# Board_Vesion_1_27_2015.net
KiCad netlist of a schematic drawn in EAGLE
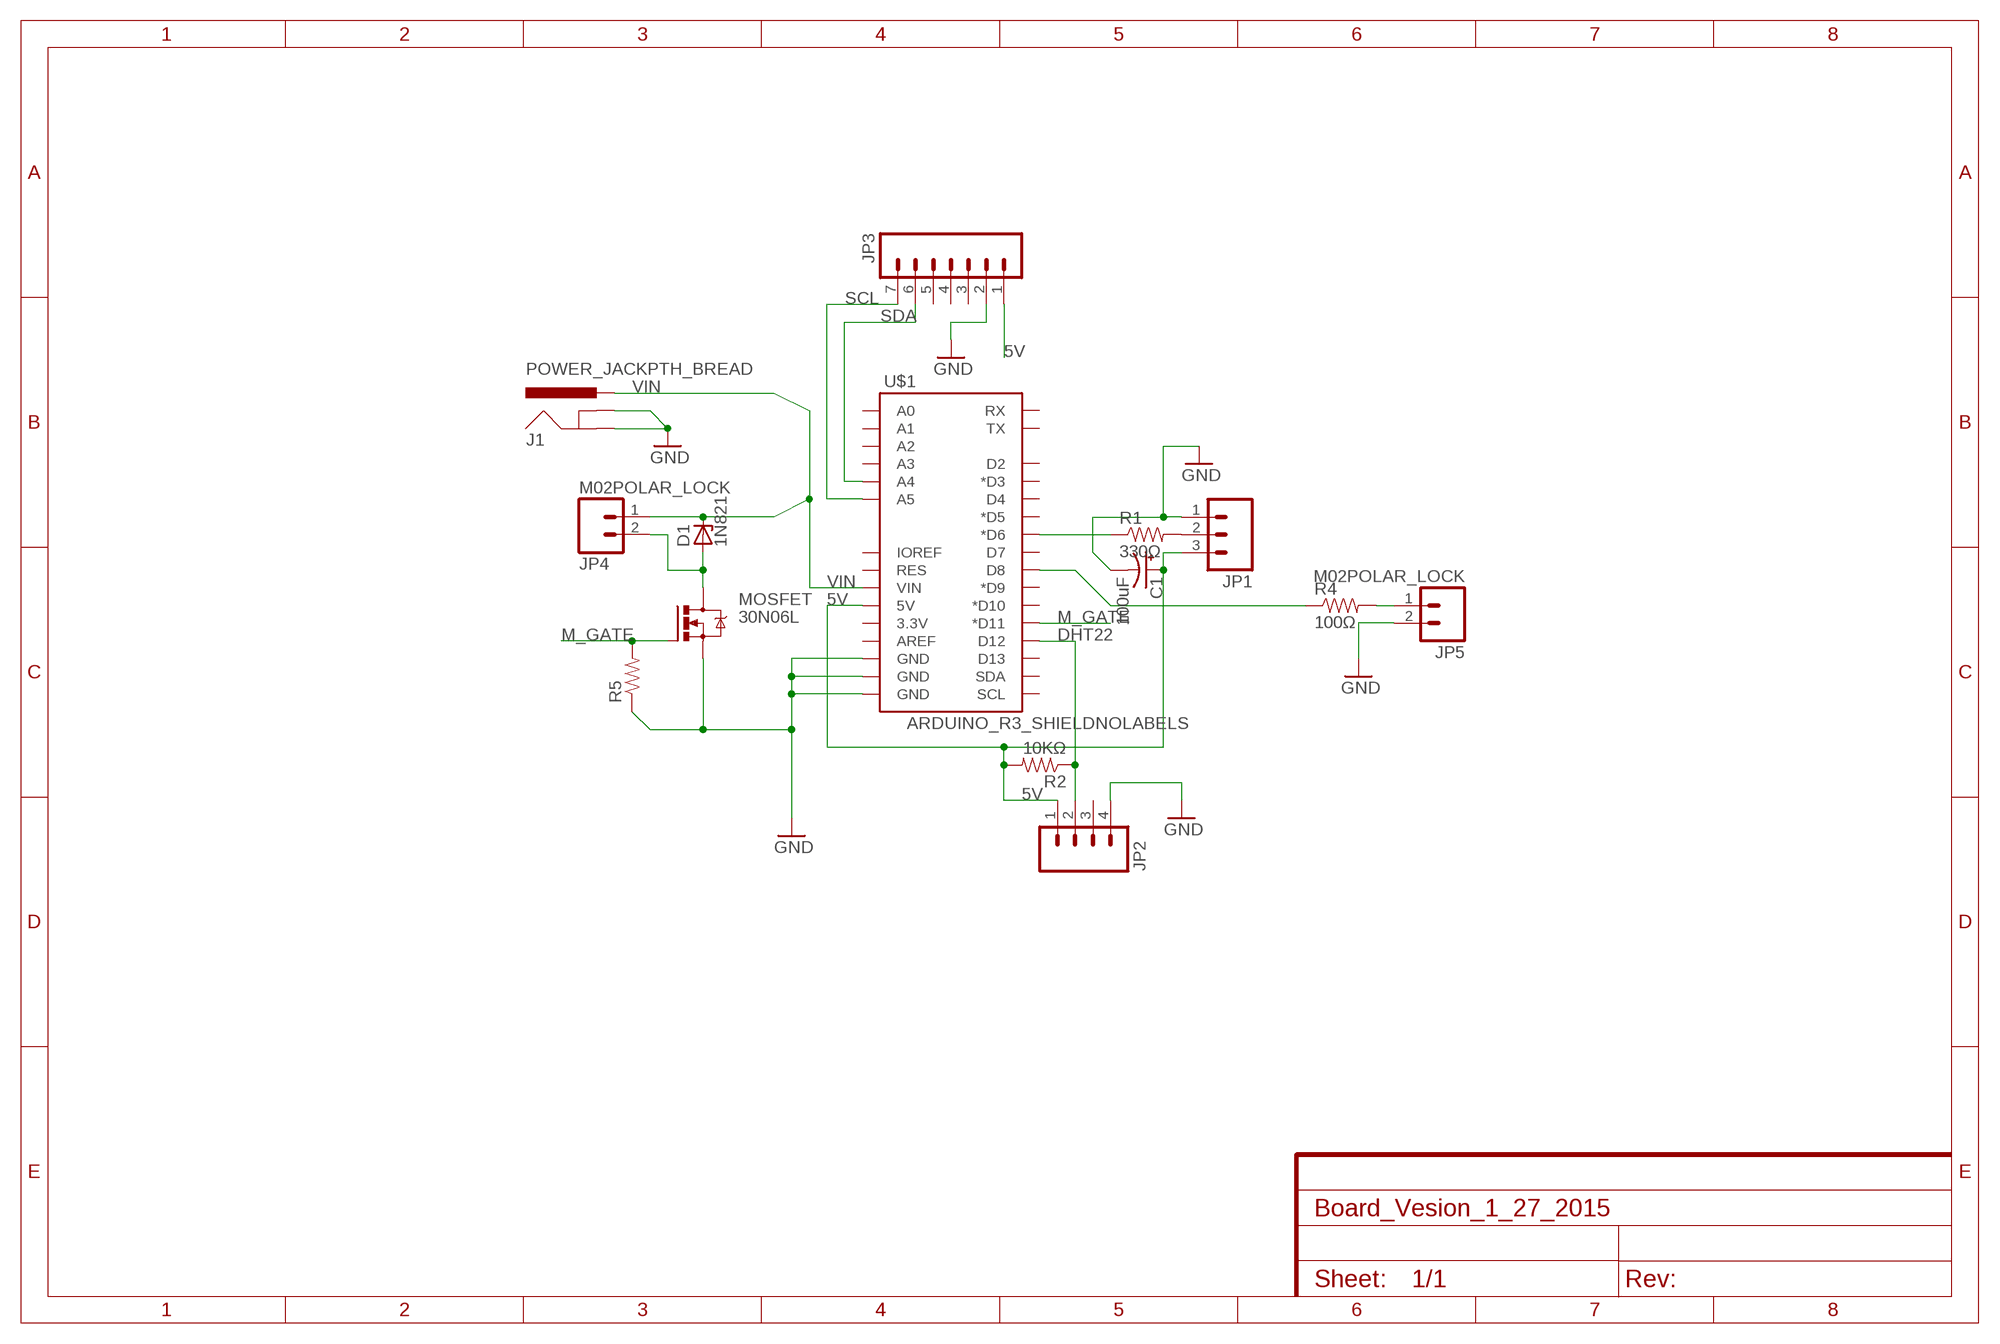
[diagram p0: schematic, sheet 1]

(export (version "E")
  (design (tool "Eeschema 10.0.6"))
  (components
    (comp (ref "C1")
      (value "100uF")
      (footprint "eagle-import:CPOL-RADIAL-10UF-25V")
      (libsource (lib "eagle-import") (part "CAP_POLPTH2"))
    )
    (comp (ref "D1")
      (value "1N821")
      (footprint "eagle-import:DO35Z10")
      (libsource (lib "eagle-import") (part "1N821"))
    )
    (comp (ref "J1")
      (value "POWER_JACKPTH_BREAD")
      (footprint "eagle-import:POWER_JACK_PTH_BREAD")
      (libsource (lib "eagle-import") (part "POWER_JACKPTH_BREAD"))
    )
    (comp (ref "JP1")
      (value "M03LOCK_LONGPADS")
      (footprint "eagle-import:1X03_LOCK_LONGPADS")
      (libsource (lib "eagle-import") (part "M03LOCK_LONGPADS"))
    )
    (comp (ref "JP2")
      (value "M04LOCK_LONGPADS")
      (footprint "eagle-import:1X04_LOCK_LONGPADS")
      (libsource (lib "eagle-import") (part "M04LOCK_LONGPADS"))
    )
    (comp (ref "JP3")
      (value "M07LOCK_LONGPADS")
      (footprint "eagle-import:1X07_LOCK_LONGPADS")
      (libsource (lib "eagle-import") (part "M07LOCK_LONGPADS"))
    )
    (comp (ref "JP4")
      (value "M02POLAR_LOCK")
      (footprint "eagle-import:MOLEX-1X2_LOCK")
      (libsource (lib "eagle-import") (part "M02POLAR_LOCK"))
    )
    (comp (ref "JP5")
      (value "M02POLAR_LOCK")
      (footprint "eagle-import:MOLEX-1X2_LOCK")
      (libsource (lib "eagle-import") (part "M02POLAR_LOCK"))
    )
    (comp (ref "MOSFET")
      (value "30N06L")
      (footprint "eagle-import:TO220BV")
      (libsource (lib "eagle-import") (part "IRF740"))
    )
    (comp (ref "R1")
      (value "330Ω")
      (footprint "eagle-import:AXIAL-0.4")
      (libsource (lib "eagle-import") (part "RESISTORPTH-1/4W"))
    )
    (comp (ref "R2")
      (value "10KΩ")
      (footprint "eagle-import:AXIAL-0.4")
      (libsource (lib "eagle-import") (part "RESISTORPTH-1/4W"))
    )
    (comp (ref "R4")
      (value "100Ω")
      (footprint "eagle-import:AXIAL-0.4")
      (libsource (lib "eagle-import") (part "SparkFun-Resistors_RESISTORPTH-1/4W"))
    )
    (comp (ref "R5")
      (value "RESISTORPTH-1W")
      (footprint "eagle-import:AXIAL-0.6")
      (libsource (lib "eagle-import") (part "SparkFun-Resistors_RESISTORPTH-1W"))
    )
    (comp (ref "U$1")
      (value "ARDUINO_R3_SHIELDNOLABELS")
      (footprint "eagle-import:UNO_R3_SHIELD_NOLABELS")
      (libsource (lib "eagle-import") (part "ARDUINO_R3_SHIELDNOLABELS"))
    )
  )
  (nets
    (net (code "1") (name "/5V") (class "Default")
      (node (ref "C1") (pin "1") (pinfunction "+_1") (pintype "passive"))
      (node (ref "JP1") (pin "3") (pinfunction "3_3") (pintype "passive"))
      (node (ref "JP2") (pin "1") (pinfunction "1_1") (pintype "passive"))
      (node (ref "JP3") (pin "1") (pinfunction "1_1") (pintype "passive"))
      (node (ref "R2") (pin "P$2") (pinfunction "2_P$2") (pintype "passive"))
      (node (ref "U$1") (pin "5V") (pinfunction "5V_5V") (pintype "bidirectional"))
    )
    (net (code "2") (name "/DHT22") (class "Default")
      (node (ref "JP2") (pin "2") (pinfunction "2_2") (pintype "passive"))
      (node (ref "R2") (pin "P$1") (pinfunction "1_P$1") (pintype "passive"))
      (node (ref "U$1") (pin "D12") (pinfunction "D12_D12") (pintype "bidirectional"))
    )
    (net (code "3") (name "/M_GATE") (class "Default")
      (node (ref "MOSFET") (pin "G") (pinfunction "G_G") (pintype "passive"))
      (node (ref "R5") (pin "P$2") (pinfunction "2_P$2") (pintype "passive"))
      (node (ref "U$1") (pin "D11") (pinfunction "*D11_D11") (pintype "bidirectional"))
    )
    (net (code "4") (name "/SCL") (class "Default")
      (node (ref "JP3") (pin "7") (pinfunction "7_7") (pintype "passive"))
      (node (ref "U$1") (pin "A5") (pinfunction "A5_A5") (pintype "bidirectional"))
    )
    (net (code "5") (name "/SDA") (class "Default")
      (node (ref "JP3") (pin "6") (pinfunction "6_6") (pintype "passive"))
      (node (ref "U$1") (pin "A4") (pinfunction "A4_A4") (pintype "bidirectional"))
    )
    (net (code "6") (name "/VIN") (class "Default")
      (node (ref "D1") (pin "C") (pinfunction "C_C") (pintype "passive"))
      (node (ref "J1") (pin "PWR") (pinfunction "PWR_PWR") (pintype "bidirectional"))
      (node (ref "JP4") (pin "1") (pinfunction "1_1") (pintype "passive"))
      (node (ref "U$1") (pin "VIN") (pinfunction "VIN_VIN") (pintype "bidirectional"))
    )
    (net (code "7") (name "GND") (class "Default")
      (node (ref "C1") (pin "2") (pinfunction "-_2") (pintype "passive"))
      (node (ref "J1") (pin "GND") (pinfunction "GND_GND") (pintype "bidirectional"))
      (node (ref "J1") (pin "GNDBREAK") (pinfunction "GNDBREAK_GNDBREAK") (pintype "bidirectional"))
      (node (ref "JP1") (pin "1") (pinfunction "1_1") (pintype "passive"))
      (node (ref "JP2") (pin "4") (pinfunction "4_4") (pintype "passive"))
      (node (ref "JP3") (pin "2") (pinfunction "2_2") (pintype "passive"))
      (node (ref "JP5") (pin "2") (pinfunction "2_2") (pintype "passive"))
      (node (ref "MOSFET") (pin "S") (pinfunction "S_S") (pintype "passive"))
      (node (ref "R5") (pin "P$1") (pinfunction "1_P$1") (pintype "passive"))
      (node (ref "U$1") (pin "GND@0") (pinfunction "GND_GND@0") (pintype "bidirectional"))
      (node (ref "U$1") (pin "GND@1") (pinfunction "GND_GND@1") (pintype "bidirectional"))
      (node (ref "U$1") (pin "GND@2") (pinfunction "GND_GND@2") (pintype "bidirectional"))
    )
    (net (code "8") (name "Net-(D1-PadA)") (class "Default")
      (node (ref "D1") (pin "A") (pinfunction "A_A") (pintype "passive"))
      (node (ref "JP4") (pin "2") (pinfunction "2_2") (pintype "passive"))
      (node (ref "MOSFET") (pin "D") (pinfunction "D_D") (pintype "passive"))
    )
    (net (code "9") (name "Net-(R1-1)") (class "Default")
      (node (ref "R1") (pin "P$1") (pinfunction "1_P$1") (pintype "passive"))
      (node (ref "U$1") (pin "D6") (pinfunction "*D6_D6") (pintype "bidirectional"))
    )
    (net (code "10") (name "Net-(R1-2)") (class "Default")
      (node (ref "JP1") (pin "2") (pinfunction "2_2") (pintype "passive"))
      (node (ref "R1") (pin "P$2") (pinfunction "2_P$2") (pintype "passive"))
    )
    (net (code "11") (name "Net-(R4-1)") (class "Default")
      (node (ref "R4") (pin "P$1") (pinfunction "1_P$1") (pintype "passive"))
      (node (ref "U$1") (pin "D8") (pinfunction "D8_D8") (pintype "bidirectional"))
    )
    (net (code "12") (name "Net-(R4-2)") (class "Default")
      (node (ref "JP5") (pin "1") (pinfunction "1_1") (pintype "passive"))
      (node (ref "R4") (pin "P$2") (pinfunction "2_P$2") (pintype "passive"))
    )
    (net (code "13") (name "unconnected-(JP2-Pad3)") (class "Default")
      (node (ref "JP2") (pin "3") (pinfunction "3_3") (pintype "passive"))
    )
    (net (code "14") (name "unconnected-(JP3-Pad3)") (class "Default")
      (node (ref "JP3") (pin "3") (pinfunction "3_3") (pintype "passive"))
    )
    (net (code "15") (name "unconnected-(JP3-Pad4)") (class "Default")
      (node (ref "JP3") (pin "4") (pinfunction "4_4") (pintype "passive"))
    )
    (net (code "16") (name "unconnected-(JP3-Pad5)") (class "Default")
      (node (ref "JP3") (pin "5") (pinfunction "5_5") (pintype "passive"))
    )
    (net (code "17") (name "unconnected-(U$1-*D3-PadD3)") (class "Default")
      (node (ref "U$1") (pin "D3") (pinfunction "*D3_D3") (pintype "bidirectional"))
    )
    (net (code "18") (name "unconnected-(U$1-*D5-PadD5)") (class "Default")
      (node (ref "U$1") (pin "D5") (pinfunction "*D5_D5") (pintype "bidirectional"))
    )
    (net (code "19") (name "unconnected-(U$1-*D9-PadD9)") (class "Default")
      (node (ref "U$1") (pin "D9") (pinfunction "*D9_D9") (pintype "bidirectional"))
    )
    (net (code "20") (name "unconnected-(U$1-*D10-PadD10)") (class "Default")
      (node (ref "U$1") (pin "D10") (pinfunction "*D10_D10") (pintype "bidirectional"))
    )
    (net (code "21") (name "unconnected-(U$1-Pad3.3V)") (class "Default")
      (node (ref "U$1") (pin "3.3V") (pinfunction "3.3V_3.3V") (pintype "bidirectional"))
    )
    (net (code "22") (name "unconnected-(U$1-PadA0)") (class "Default")
      (node (ref "U$1") (pin "A0") (pinfunction "A0_A0") (pintype "bidirectional"))
    )
    (net (code "23") (name "unconnected-(U$1-PadA1)") (class "Default")
      (node (ref "U$1") (pin "A1") (pinfunction "A1_A1") (pintype "bidirectional"))
    )
    (net (code "24") (name "unconnected-(U$1-PadA2)") (class "Default")
      (node (ref "U$1") (pin "A2") (pinfunction "A2_A2") (pintype "bidirectional"))
    )
    (net (code "25") (name "unconnected-(U$1-PadA3)") (class "Default")
      (node (ref "U$1") (pin "A3") (pinfunction "A3_A3") (pintype "bidirectional"))
    )
    (net (code "26") (name "unconnected-(U$1-PadAREF)") (class "Default")
      (node (ref "U$1") (pin "AREF") (pinfunction "AREF_AREF") (pintype "bidirectional"))
    )
    (net (code "27") (name "unconnected-(U$1-PadD2)") (class "Default")
      (node (ref "U$1") (pin "D2") (pinfunction "D2_D2") (pintype "bidirectional"))
    )
    (net (code "28") (name "unconnected-(U$1-PadD4)") (class "Default")
      (node (ref "U$1") (pin "D4") (pinfunction "D4_D4") (pintype "bidirectional"))
    )
    (net (code "29") (name "unconnected-(U$1-PadD7)") (class "Default")
      (node (ref "U$1") (pin "D7") (pinfunction "D7_D7") (pintype "bidirectional"))
    )
    (net (code "30") (name "unconnected-(U$1-PadD13)") (class "Default")
      (node (ref "U$1") (pin "D13") (pinfunction "D13_D13") (pintype "bidirectional"))
    )
    (net (code "31") (name "unconnected-(U$1-PadIOREF)") (class "Default")
      (node (ref "U$1") (pin "IOREF") (pinfunction "IOREF_IOREF") (pintype "bidirectional"))
    )
    (net (code "32") (name "unconnected-(U$1-PadRES)") (class "Default")
      (node (ref "U$1") (pin "RES") (pinfunction "RES_RES") (pintype "bidirectional"))
    )
    (net (code "33") (name "unconnected-(U$1-PadRX)") (class "Default")
      (node (ref "U$1") (pin "RX") (pinfunction "RX_RX") (pintype "bidirectional"))
    )
    (net (code "34") (name "unconnected-(U$1-PadSCL)") (class "Default")
      (node (ref "U$1") (pin "SCL") (pinfunction "SCL_SCL") (pintype "bidirectional"))
    )
    (net (code "35") (name "unconnected-(U$1-PadSDA)") (class "Default")
      (node (ref "U$1") (pin "SDA") (pinfunction "SDA_SDA") (pintype "bidirectional"))
    )
    (net (code "36") (name "unconnected-(U$1-PadTX)") (class "Default")
      (node (ref "U$1") (pin "TX") (pinfunction "TX_TX") (pintype "bidirectional"))
    )
  )
)
